# MSP.net
KiCad netlist of a schematic drawn in Altium Designer
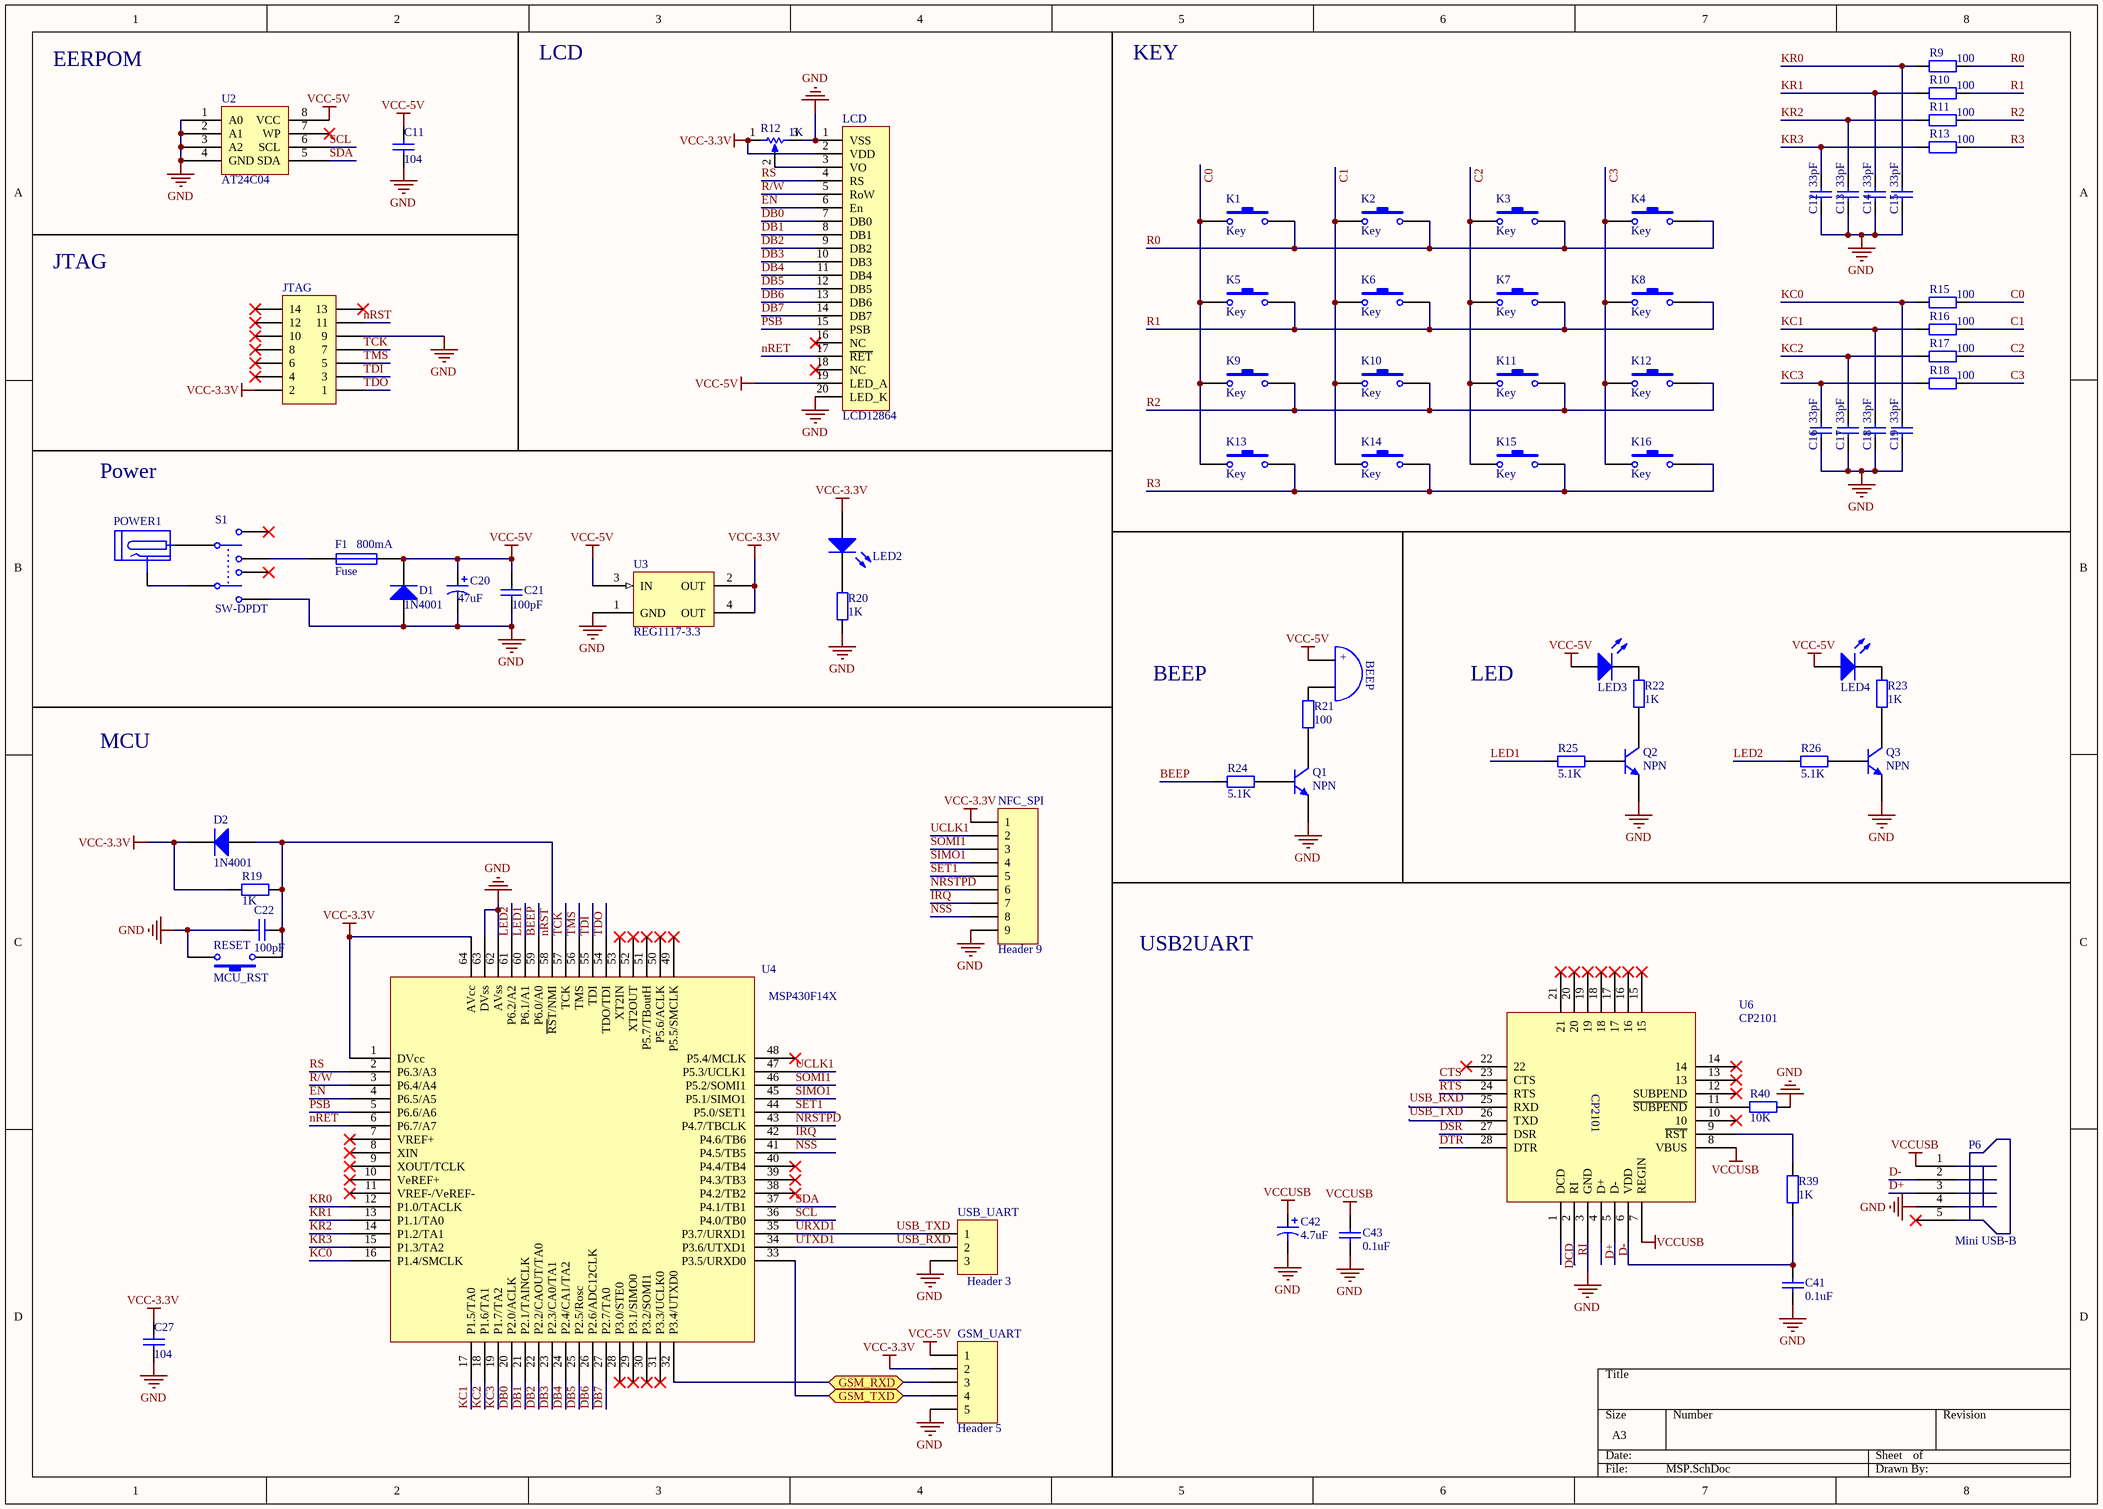
[diagram p0: MSP.SchDoc]

(export (version "E")
  (design (tool "Eeschema 10.0.6"))
  (components
    (comp (ref "BEEP1") (value "BEEP") (footprint "BEEP") (libsource (lib "common") (part "BEEP")))
    (comp (ref "C11")
      (value "104")
      (footprint "1608[0603]")
      (description "Capacitor")
      (fields (field (name "Comment") "Cap") (field (name "PUBLISHER") "Altium Limited"))
      (libsource (lib "common") (part "Cap"))
    )
    (comp (ref "C12")
      (value "33pF")
      (footprint "1608[0603]")
      (description "Capacitor")
      (fields (field (name "Comment") "Cap") (field (name "PUBLISHER") "Altium Limited"))
      (libsource (lib "common") (part "Cap"))
    )
    (comp (ref "C13")
      (value "33pF")
      (footprint "1608[0603]")
      (description "Capacitor")
      (fields (field (name "Comment") "Cap") (field (name "PUBLISHER") "Altium Limited"))
      (libsource (lib "common") (part "Cap"))
    )
    (comp (ref "C14")
      (value "33pF")
      (footprint "1608[0603]")
      (description "Capacitor")
      (fields (field (name "Comment") "Cap") (field (name "PUBLISHER") "Altium Limited"))
      (libsource (lib "common") (part "Cap"))
    )
    (comp (ref "C15")
      (value "33pF")
      (footprint "1608[0603]")
      (description "Capacitor")
      (fields (field (name "Comment") "Cap") (field (name "PUBLISHER") "Altium Limited"))
      (libsource (lib "common") (part "Cap"))
    )
    (comp (ref "C16")
      (value "33pF")
      (footprint "1608[0603]")
      (description "Capacitor")
      (fields (field (name "Comment") "Cap") (field (name "PUBLISHER") "Altium Limited"))
      (libsource (lib "common") (part "Cap"))
    )
    (comp (ref "C17")
      (value "33pF")
      (footprint "1608[0603]")
      (description "Capacitor")
      (fields (field (name "Comment") "Cap") (field (name "PUBLISHER") "Altium Limited"))
      (libsource (lib "common") (part "Cap"))
    )
    (comp (ref "C18")
      (value "33pF")
      (footprint "1608[0603]")
      (description "Capacitor")
      (fields (field (name "Comment") "Cap") (field (name "PUBLISHER") "Altium Limited"))
      (libsource (lib "common") (part "Cap"))
    )
    (comp (ref "C19")
      (value "33pF")
      (footprint "1608[0603]")
      (description "Capacitor")
      (fields (field (name "Comment") "Cap") (field (name "PUBLISHER") "Altium Limited"))
      (libsource (lib "common") (part "Cap"))
    )
    (comp (ref "C20")
      (value "47uF")
      (footprint "Standard:B")
      (description "Polarized Capacitor (Axial)")
      (fields (field (name "Comment") "CAP POL") (field (name "PUBLISHER") "Altium Limited"))
      (libsource (lib "common") (part "CAP POL"))
    )
    (comp (ref "C21")
      (value "100pF")
      (footprint "1608[0603]")
      (description "Capacitor")
      (fields (field (name "Comment") "Cap") (field (name "PUBLISHER") "Altium Limited"))
      (libsource (lib "common") (part "Cap"))
    )
    (comp (ref "C22")
      (value "100pF")
      (footprint "1608[0603]")
      (description "Capacitor")
      (fields (field (name "Comment") "Cap") (field (name "PUBLISHER") "Altium Limited"))
      (libsource (lib "common") (part "Cap"))
    )
    (comp (ref "C27")
      (value "104")
      (footprint "1608[0603]")
      (description "Capacitor")
      (fields (field (name "Comment") "Cap") (field (name "PUBLISHER") "Altium Limited"))
      (libsource (lib "common") (part "Cap"))
    )
    (comp (ref "C41")
      (value "0.1uF")
      (footprint "1608[0603]")
      (description "Capacitor")
      (fields (field (name "Comment") "Cap") (field (name "PUBLISHER") "Altium Limited"))
      (libsource (lib "common") (part "Cap"))
    )
    (comp (ref "C42")
      (value "4.7uF")
      (footprint "Standard:B")
      (description "Polarized Capacitor (Axial)")
      (fields (field (name "Comment") "CAP POL") (field (name "PUBLISHER") "Altium Limited"))
      (libsource (lib "common") (part "CAP POL"))
    )
    (comp (ref "C43")
      (value "0.1uF")
      (footprint "1608[0603]")
      (description "Capacitor")
      (fields (field (name "Comment") "Cap") (field (name "PUBLISHER") "Altium Limited"))
      (libsource (lib "common") (part "Cap"))
    )
    (comp (ref "D1")
      (value "1N4001")
      (footprint "1608[0603] - POL")
      (description "1 Amp General Purpose Rectifier")
      (fields (field (name "PUBLISHER") "Altium Limited"))
      (libsource (lib "common") (part "Diode 1N4001"))
    )
    (comp (ref "D2")
      (value "1N4001")
      (footprint "1608[0603] - POL")
      (description "1 Amp General Purpose Rectifier")
      (fields (field (name "PUBLISHER") "Altium Limited"))
      (libsource (lib "common") (part "Diode 1N4001"))
    )
    (comp (ref "F1")
      (value "Fuse")
      (footprint "2012[0805]")
      (fields (field (name "CURRENT") "800mA"))
      (libsource (lib "common") (part "FUSE1"))
    )
    (comp (ref "GSM_UART")
      (value "Header 5")
      (footprint "HDR1X5")
      (description "Header, 5-Pin")
      (fields (field (name "PUBLISHER") "Altium Limited"))
      (libsource (lib "Miscellaneous Connectors") (part "Header 5"))
    )
    (comp (ref "JTAG")
      (value "Header 7X2H")
      (footprint "HDR2X7H")
      (description "Header, 7-Pin, Dual row, Right Angle")
      (fields (field (name "PUBLISHER") "Altium Limited"))
      (libsource (lib "Miscellaneous Connectors") (part "Header 7X2H"))
    )
    (comp (ref "K1") (value "Key") (footprint "Key-4") (libsource (lib "*") (part "SW-PB")))
    (comp (ref "K2") (value "Key") (footprint "Key-4") (libsource (lib "common") (part "SW-PB")))
    (comp (ref "K3") (value "Key") (footprint "Key-4") (libsource (lib "common") (part "SW-PB")))
    (comp (ref "K4") (value "Key") (footprint "Key-4") (libsource (lib "common") (part "SW-PB")))
    (comp (ref "K5") (value "Key") (footprint "Key-4") (libsource (lib "common") (part "SW-PB")))
    (comp (ref "K6") (value "Key") (footprint "Key-4") (libsource (lib "common") (part "SW-PB")))
    (comp (ref "K7") (value "Key") (footprint "Key-4") (libsource (lib "common") (part "SW-PB")))
    (comp (ref "K8") (value "Key") (footprint "Key-4") (libsource (lib "common") (part "SW-PB")))
    (comp (ref "K9") (value "Key") (footprint "Key-4") (libsource (lib "common") (part "SW-PB")))
    (comp (ref "K10") (value "Key") (footprint "Key-4") (libsource (lib "common") (part "SW-PB")))
    (comp (ref "K11") (value "Key") (footprint "Key-4") (libsource (lib "common") (part "SW-PB")))
    (comp (ref "K12") (value "Key") (footprint "Key-4") (libsource (lib "common") (part "SW-PB")))
    (comp (ref "K13") (value "Key") (footprint "Key-4") (libsource (lib "common") (part "SW-PB")))
    (comp (ref "K14") (value "Key") (footprint "Key-4") (libsource (lib "common") (part "SW-PB")))
    (comp (ref "K15") (value "Key") (footprint "Key-4") (libsource (lib "common") (part "SW-PB")))
    (comp (ref "K16") (value "Key") (footprint "Key-4") (libsource (lib "common") (part "SW-PB")))
    (comp (ref "LCD") (value "LCD12864") (footprint "LCD-20PIN") (libsource (lib "*") (part "LCD12864")))
    (comp (ref "LED2") (value "LED") (footprint "2012[0805] - POL") (libsource (lib "common") (part "LED")))
    (comp (ref "LED3") (value "LED") (footprint "2012[0805] - POL") (libsource (lib "common") (part "LED")))
    (comp (ref "LED4") (value "LED") (footprint "2012[0805] - POL") (libsource (lib "common") (part "LED")))
    (comp (ref "NFC_SPI")
      (value "Header 9")
      (footprint "HDR1X9")
      (description "Header, 9-Pin")
      (fields (field (name "PUBLISHER") "Altium Limited"))
      (libsource (lib "Miscellaneous Connectors") (part "Header 9"))
    )
    (comp (ref "P6")
      (value "Mini USB-B")
      (footprint "MINI USB-501")
      (description "Mini USB Type B")
      (libsource (lib "USB2UART") (part "USB"))
    )
    (comp (ref "POWER1") (value "POWER") (footprint "POWER") (libsource (lib "51ExpBoard") (part "POWER")))
    (comp (ref "Q1") (value "NPN") (footprint "SOT23-3L") (libsource (lib "common") (part "NPN")))
    (comp (ref "Q2") (value "NPN") (footprint "SOT23-3L") (libsource (lib "common") (part "NPN")))
    (comp (ref "Q3") (value "NPN") (footprint "SOT23-3L") (libsource (lib "common") (part "NPN")))
    (comp (ref "R9")
      (value "100")
      (footprint "1608[0603]")
      (description "Resistor")
      (fields (field (name "Comment") "RES") (field (name "PUBLISHER") "Altium Limited"))
      (libsource (lib "common") (part "RES"))
    )
    (comp (ref "R10")
      (value "100")
      (footprint "1608[0603]")
      (description "Resistor")
      (fields (field (name "Comment") "RES") (field (name "PUBLISHER") "Altium Limited"))
      (libsource (lib "common") (part "RES"))
    )
    (comp (ref "R11")
      (value "100")
      (footprint "1608[0603]")
      (description "Resistor")
      (fields (field (name "Comment") "RES") (field (name "PUBLISHER") "Altium Limited"))
      (libsource (lib "common") (part "RES"))
    )
    (comp (ref "R12")
      (value "1K")
      (footprint "VR5")
      (description "Potentiometer")
      (fields (field (name "Comment") "RPot") (field (name "PUBLISHER") "Altium Limited"))
      (libsource (lib "Miscellaneous Devices") (part "RPot"))
    )
    (comp (ref "R13")
      (value "100")
      (footprint "1608[0603]")
      (description "Resistor")
      (fields (field (name "Comment") "RES") (field (name "PUBLISHER") "Altium Limited"))
      (libsource (lib "common") (part "RES"))
    )
    (comp (ref "R15")
      (value "100")
      (footprint "1608[0603]")
      (description "Resistor")
      (fields (field (name "Comment") "RES") (field (name "PUBLISHER") "Altium Limited"))
      (libsource (lib "common") (part "RES"))
    )
    (comp (ref "R16")
      (value "100")
      (footprint "1608[0603]")
      (description "Resistor")
      (fields (field (name "Comment") "RES") (field (name "PUBLISHER") "Altium Limited"))
      (libsource (lib "common") (part "RES"))
    )
    (comp (ref "R17")
      (value "100")
      (footprint "1608[0603]")
      (description "Resistor")
      (fields (field (name "Comment") "RES") (field (name "PUBLISHER") "Altium Limited"))
      (libsource (lib "common") (part "RES"))
    )
    (comp (ref "R18")
      (value "100")
      (footprint "1608[0603]")
      (description "Resistor")
      (fields (field (name "Comment") "RES") (field (name "PUBLISHER") "Altium Limited"))
      (libsource (lib "common") (part "RES"))
    )
    (comp (ref "R19")
      (value "1K")
      (footprint "1608[0603]")
      (description "Resistor")
      (fields (field (name "Comment") "Res") (field (name "PUBLISHER") "Altium Limited"))
      (libsource (lib "") (part "RES_2"))
    )
    (comp (ref "R20")
      (value "1K")
      (footprint "1608[0603]")
      (description "Resistor")
      (fields (field (name "Comment") "Res") (field (name "PUBLISHER") "Altium Limited"))
      (libsource (lib "") (part "RES_1"))
    )
    (comp (ref "R21")
      (value "100")
      (footprint "1608[0603]")
      (description "Resistor")
      (fields (field (name "Comment") "Res") (field (name "PUBLISHER") "Altium Limited"))
      (libsource (lib "") (part "RES_1"))
    )
    (comp (ref "R22")
      (value "1K")
      (footprint "1608[0603]")
      (description "Resistor")
      (fields (field (name "Comment") "Res") (field (name "PUBLISHER") "Altium Limited"))
      (libsource (lib "") (part "RES_1"))
    )
    (comp (ref "R23")
      (value "1K")
      (footprint "1608[0603]")
      (description "Resistor")
      (fields (field (name "Comment") "Res") (field (name "PUBLISHER") "Altium Limited"))
      (libsource (lib "") (part "RES_1"))
    )
    (comp (ref "R24")
      (value "5.1K")
      (footprint "1608[0603]")
      (description "Resistor")
      (fields (field (name "Comment") "Res") (field (name "PUBLISHER") "Altium Limited"))
      (libsource (lib "common") (part "RES"))
    )
    (comp (ref "R25")
      (value "5.1K")
      (footprint "1608[0603]")
      (description "Resistor")
      (fields (field (name "Comment") "Res") (field (name "PUBLISHER") "Altium Limited"))
      (libsource (lib "common") (part "RES"))
    )
    (comp (ref "R26")
      (value "5.1K")
      (footprint "1608[0603]")
      (description "Resistor")
      (fields (field (name "Comment") "Res") (field (name "PUBLISHER") "Altium Limited"))
      (libsource (lib "common") (part "RES"))
    )
    (comp (ref "R39")
      (value "1K")
      (footprint "1608[0603]")
      (description "Resistor")
      (fields (field (name "Comment") "Res") (field (name "PUBLISHER") "Altium Limited"))
      (libsource (lib "") (part "RES_3"))
    )
    (comp (ref "R40")
      (value "10K")
      (footprint "1608[0603]")
      (description "Resistor")
      (fields (field (name "Comment") "Res") (field (name "PUBLISHER") "Altium Limited"))
      (libsource (lib "common") (part "RES"))
    )
    (comp (ref "RESET") (value "MCU_RST") (footprint "Key-4") (libsource (lib "common") (part "SW-PB")))
    (comp (ref "S1")
      (value "SW-DPDT")
      (footprint "SW-DPDT")
      (description "Double-Pole, Double-Throw Switch")
      (fields (field (name "PUBLISHER") "Altium Limited"))
      (libsource (lib "common") (part "SW-DPDT"))
    )
    (comp (ref "U2")
      (value "AT24C04")
      (footprint "SOIC127P600-8AN")
      (libsource (lib "common") (part "AT24C04"))
    )
    (comp (ref "U3")
      (value "REG1117-3.3")
      (footprint "SOT223")
      (libsource (lib "MYSELF") (part "REG1117-3.3"))
    )
    (comp (ref "U4")
      (value "MSP430F14X")
      (footprint "SQFP50P1200X1200-64N")
      (libsource (lib "*") (part "MSP430F14X"))
    )
    (comp (ref "U6")
      (value "CP2101")
      (footprint "QFN50P500X500-28VAN")
      (libsource (lib "USB2UART") (part "CP2101"))
    )
    (comp (ref "USB_UART")
      (value "Header 3")
      (footprint "HDR1X3")
      (description "Header, 3-Pin")
      (fields (field (name "PUBLISHER") "Altium Limited"))
      (libsource (lib "Miscellaneous Connectors") (part "Header 3"))
    )
  )
  (nets
    (net (code "1") (name "/BEEP") (class "Default")
      (node (ref "R24") (pin "1") (pinfunction "1_1") (pintype "passive"))
      (node (ref "U4") (pin "59") (pinfunction "P6.0/A0_59") (pintype "power_in"))
    )
    (net (code "2") (name "/C0") (class "Default")
      (node (ref "K1") (pin "1") (pinfunction "1_1") (pintype "passive"))
      (node (ref "K13") (pin "1") (pinfunction "1_1") (pintype "passive"))
      (node (ref "K5") (pin "1") (pinfunction "1_1") (pintype "passive"))
      (node (ref "K9") (pin "1") (pinfunction "1_1") (pintype "passive"))
      (node (ref "R15") (pin "2") (pinfunction "2_2") (pintype "passive"))
    )
    (net (code "3") (name "/C1") (class "Default")
      (node (ref "K10") (pin "1") (pinfunction "1_1") (pintype "passive"))
      (node (ref "K14") (pin "1") (pinfunction "1_1") (pintype "passive"))
      (node (ref "K2") (pin "1") (pinfunction "1_1") (pintype "passive"))
      (node (ref "K6") (pin "1") (pinfunction "1_1") (pintype "passive"))
      (node (ref "R16") (pin "2") (pinfunction "2_2") (pintype "passive"))
    )
    (net (code "4") (name "/C2") (class "Default")
      (node (ref "K11") (pin "1") (pinfunction "1_1") (pintype "passive"))
      (node (ref "K15") (pin "1") (pinfunction "1_1") (pintype "passive"))
      (node (ref "K3") (pin "1") (pinfunction "1_1") (pintype "passive"))
      (node (ref "K7") (pin "1") (pinfunction "1_1") (pintype "passive"))
      (node (ref "R17") (pin "2") (pinfunction "2_2") (pintype "passive"))
    )
    (net (code "5") (name "/C3") (class "Default")
      (node (ref "K12") (pin "1") (pinfunction "1_1") (pintype "passive"))
      (node (ref "K16") (pin "1") (pinfunction "1_1") (pintype "passive"))
      (node (ref "K4") (pin "1") (pinfunction "1_1") (pintype "passive"))
      (node (ref "K8") (pin "1") (pinfunction "1_1") (pintype "passive"))
      (node (ref "R18") (pin "2") (pinfunction "2_2") (pintype "passive"))
    )
    (net (code "6") (name "/CTS") (class "Default")
      (node (ref "U6") (pin "23") (pinfunction "CTS_23") (pintype "passive"))
    )
    (net (code "7") (name "/D+") (class "Default")
      (node (ref "P6") (pin "3") (pinfunction "3_3") (pintype "passive"))
      (node (ref "U6") (pin "4") (pinfunction "D+_4") (pintype "passive"))
    )
    (net (code "8") (name "/D-") (class "Default")
      (node (ref "P6") (pin "2") (pinfunction "2_2") (pintype "passive"))
      (node (ref "U6") (pin "5") (pinfunction "D-_5") (pintype "passive"))
    )
    (net (code "9") (name "/DB0") (class "Default")
      (node (ref "LCD") (pin "7") (pinfunction "DB0_7") (pintype "passive"))
      (node (ref "U4") (pin "20") (pinfunction "P2.0/ACLK_20") (pintype "power_in"))
    )
    (net (code "10") (name "/DB1") (class "Default")
      (node (ref "LCD") (pin "8") (pinfunction "DB1_8") (pintype "passive"))
      (node (ref "U4") (pin "21") (pinfunction "P2.1/TAINCLK_21") (pintype "power_in"))
    )
    (net (code "11") (name "/DB2") (class "Default")
      (node (ref "LCD") (pin "9") (pinfunction "DB2_9") (pintype "passive"))
      (node (ref "U4") (pin "22") (pinfunction "P2.2/CAOUT/TA0_22") (pintype "power_in"))
    )
    (net (code "12") (name "/DB3") (class "Default")
      (node (ref "LCD") (pin "10") (pinfunction "DB3_10") (pintype "passive"))
      (node (ref "U4") (pin "23") (pinfunction "P2.3/CA0/TA1_23") (pintype "power_in"))
    )
    (net (code "13") (name "/DB4") (class "Default")
      (node (ref "LCD") (pin "11") (pinfunction "DB4_11") (pintype "passive"))
      (node (ref "U4") (pin "24") (pinfunction "P2.4/CA1/TA2_24") (pintype "power_in"))
    )
    (net (code "14") (name "/DB5") (class "Default")
      (node (ref "LCD") (pin "12") (pinfunction "DB5_12") (pintype "passive"))
      (node (ref "U4") (pin "25") (pinfunction "P2.5/Rosc_25") (pintype "power_in"))
    )
    (net (code "15") (name "/DB6") (class "Default")
      (node (ref "LCD") (pin "13") (pinfunction "DB6_13") (pintype "passive"))
      (node (ref "U4") (pin "26") (pinfunction "P2.6/ADC12CLK_26") (pintype "power_in"))
    )
    (net (code "16") (name "/DB7") (class "Default")
      (node (ref "LCD") (pin "14") (pinfunction "DB7_14") (pintype "passive"))
      (node (ref "U4") (pin "27") (pinfunction "P2.7/TA0_27") (pintype "power_in"))
    )
    (net (code "17") (name "/DCD") (class "Default")
      (node (ref "U6") (pin "1") (pinfunction "DCD_1") (pintype "passive"))
    )
    (net (code "18") (name "/DSR") (class "Default")
      (node (ref "U6") (pin "27") (pinfunction "DSR_27") (pintype "passive"))
    )
    (net (code "19") (name "/DTR") (class "Default")
      (node (ref "U6") (pin "28") (pinfunction "DTR_28") (pintype "passive"))
    )
    (net (code "20") (name "/EN") (class "Default")
      (node (ref "LCD") (pin "6") (pinfunction "En_6") (pintype "passive"))
      (node (ref "U4") (pin "4") (pinfunction "P6.5/A5_4") (pintype "power_in"))
    )
    (net (code "21") (name "/GSM_RXD") (class "Default")
      (node (ref "GSM_UART") (pin "3") (pinfunction "3_3") (pintype "passive"))
      (node (ref "U4") (pin "32") (pinfunction "P3.4/UTXD0_32") (pintype "power_in"))
    )
    (net (code "22") (name "/GSM_TXD") (class "Default")
      (node (ref "GSM_UART") (pin "4") (pinfunction "4_4") (pintype "passive"))
      (node (ref "U4") (pin "33") (pinfunction "P3.5/URXD0_33") (pintype "power_in"))
    )
    (net (code "23") (name "/IRQ") (class "Default")
      (node (ref "NFC_SPI") (pin "7") (pinfunction "7_7") (pintype "passive"))
      (node (ref "U4") (pin "42") (pinfunction "P4.6/TB6_42") (pintype "power_in"))
    )
    (net (code "24") (name "/KC0") (class "Default")
      (node (ref "C19") (pin "1") (pinfunction "1_1") (pintype "passive"))
      (node (ref "R15") (pin "1") (pinfunction "1_1") (pintype "passive"))
      (node (ref "U4") (pin "16") (pinfunction "P1.4/SMCLK_16") (pintype "power_in"))
    )
    (net (code "25") (name "/KC1") (class "Default")
      (node (ref "C18") (pin "1") (pinfunction "1_1") (pintype "passive"))
      (node (ref "R16") (pin "1") (pinfunction "1_1") (pintype "passive"))
      (node (ref "U4") (pin "17") (pinfunction "P1.5/TA0_17") (pintype "power_in"))
    )
    (net (code "26") (name "/KC2") (class "Default")
      (node (ref "C17") (pin "1") (pinfunction "1_1") (pintype "passive"))
      (node (ref "R17") (pin "1") (pinfunction "1_1") (pintype "passive"))
      (node (ref "U4") (pin "18") (pinfunction "P1.6/TA1_18") (pintype "power_in"))
    )
    (net (code "27") (name "/KC3") (class "Default")
      (node (ref "C16") (pin "1") (pinfunction "1_1") (pintype "passive"))
      (node (ref "R18") (pin "1") (pinfunction "1_1") (pintype "passive"))
      (node (ref "U4") (pin "19") (pinfunction "P1.7/TA2_19") (pintype "power_in"))
    )
    (net (code "28") (name "/KR0") (class "Default")
      (node (ref "C15") (pin "1") (pinfunction "1_1") (pintype "passive"))
      (node (ref "R9") (pin "1") (pinfunction "1_1") (pintype "passive"))
      (node (ref "U4") (pin "12") (pinfunction "P1.0/TACLK_12") (pintype "power_in"))
    )
    (net (code "29") (name "/KR1") (class "Default")
      (node (ref "C14") (pin "1") (pinfunction "1_1") (pintype "passive"))
      (node (ref "R10") (pin "1") (pinfunction "1_1") (pintype "passive"))
      (node (ref "U4") (pin "13") (pinfunction "P1.1/TA0_13") (pintype "power_in"))
    )
    (net (code "30") (name "/KR2") (class "Default")
      (node (ref "C13") (pin "1") (pinfunction "1_1") (pintype "passive"))
      (node (ref "R11") (pin "1") (pinfunction "1_1") (pintype "passive"))
      (node (ref "U4") (pin "14") (pinfunction "P1.2/TA1_14") (pintype "power_in"))
    )
    (net (code "31") (name "/KR3") (class "Default")
      (node (ref "C12") (pin "1") (pinfunction "1_1") (pintype "passive"))
      (node (ref "R13") (pin "1") (pinfunction "1_1") (pintype "passive"))
      (node (ref "U4") (pin "15") (pinfunction "P1.3/TA2_15") (pintype "power_in"))
    )
    (net (code "32") (name "/LED1") (class "Default")
      (node (ref "R25") (pin "1") (pinfunction "1_1") (pintype "passive"))
      (node (ref "U4") (pin "60") (pinfunction "P6.1/A1_60") (pintype "power_in"))
    )
    (net (code "33") (name "/LED2") (class "Default")
      (node (ref "R26") (pin "1") (pinfunction "1_1") (pintype "passive"))
      (node (ref "U4") (pin "61") (pinfunction "P6.2/A2_61") (pintype "power_in"))
    )
    (net (code "34") (name "/NRSTPD") (class "Default")
      (node (ref "NFC_SPI") (pin "6") (pinfunction "6_6") (pintype "passive"))
      (node (ref "U4") (pin "43") (pinfunction "P4.7/TBCLK_43") (pintype "power_in"))
    )
    (net (code "35") (name "/NSS") (class "Default")
      (node (ref "NFC_SPI") (pin "8") (pinfunction "8_8") (pintype "passive"))
      (node (ref "U4") (pin "41") (pinfunction "P4.5/TB5_41") (pintype "power_in"))
    )
    (net (code "36") (name "/PSB") (class "Default")
      (node (ref "LCD") (pin "15") (pinfunction "PSB_15") (pintype "passive"))
      (node (ref "U4") (pin "5") (pinfunction "P6.6/A6_5") (pintype "power_in"))
    )
    (net (code "37") (name "/R0") (class "Default")
      (node (ref "K1") (pin "2") (pinfunction "2_2") (pintype "passive"))
      (node (ref "K2") (pin "2") (pinfunction "2_2") (pintype "passive"))
      (node (ref "K3") (pin "2") (pinfunction "2_2") (pintype "passive"))
      (node (ref "K4") (pin "2") (pinfunction "2_2") (pintype "passive"))
      (node (ref "R9") (pin "2") (pinfunction "2_2") (pintype "passive"))
    )
    (net (code "38") (name "/R1") (class "Default")
      (node (ref "K5") (pin "2") (pinfunction "2_2") (pintype "passive"))
      (node (ref "K6") (pin "2") (pinfunction "2_2") (pintype "passive"))
      (node (ref "K7") (pin "2") (pinfunction "2_2") (pintype "passive"))
      (node (ref "K8") (pin "2") (pinfunction "2_2") (pintype "passive"))
      (node (ref "R10") (pin "2") (pinfunction "2_2") (pintype "passive"))
    )
    (net (code "39") (name "/R2") (class "Default")
      (node (ref "K10") (pin "2") (pinfunction "2_2") (pintype "passive"))
      (node (ref "K11") (pin "2") (pinfunction "2_2") (pintype "passive"))
      (node (ref "K12") (pin "2") (pinfunction "2_2") (pintype "passive"))
      (node (ref "K9") (pin "2") (pinfunction "2_2") (pintype "passive"))
      (node (ref "R11") (pin "2") (pinfunction "2_2") (pintype "passive"))
    )
    (net (code "40") (name "/R3") (class "Default")
      (node (ref "K13") (pin "2") (pinfunction "2_2") (pintype "passive"))
      (node (ref "K14") (pin "2") (pinfunction "2_2") (pintype "passive"))
      (node (ref "K15") (pin "2") (pinfunction "2_2") (pintype "passive"))
      (node (ref "K16") (pin "2") (pinfunction "2_2") (pintype "passive"))
      (node (ref "R13") (pin "2") (pinfunction "2_2") (pintype "passive"))
    )
    (net (code "41") (name "/RI") (class "Default")
      (node (ref "U6") (pin "2") (pinfunction "RI_2") (pintype "passive"))
    )
    (net (code "42") (name "/RS") (class "Default")
      (node (ref "LCD") (pin "4") (pinfunction "RS_4") (pintype "passive"))
      (node (ref "U4") (pin "2") (pinfunction "P6.3/A3_2") (pintype "power_in"))
    )
    (net (code "43") (name "/RTS") (class "Default")
      (node (ref "U6") (pin "24") (pinfunction "RTS_24") (pintype "passive"))
    )
    (net (code "44") (name "/R{slash}W") (class "Default")
      (node (ref "LCD") (pin "5") (pinfunction "RoW_5") (pintype "passive"))
      (node (ref "U4") (pin "3") (pinfunction "P6.4/A4_3") (pintype "power_in"))
    )
    (net (code "45") (name "/SCL") (class "Default")
      (node (ref "U2") (pin "6") (pinfunction "SCL_6") (pintype "passive"))
      (node (ref "U4") (pin "36") (pinfunction "P4.0/TB0_36") (pintype "power_in"))
    )
    (net (code "46") (name "/SDA") (class "Default")
      (node (ref "U2") (pin "5") (pinfunction "SDA_5") (pintype "passive"))
      (node (ref "U4") (pin "37") (pinfunction "P4.1/TB1_37") (pintype "power_in"))
    )
    (net (code "47") (name "/SET1") (class "Default")
      (node (ref "NFC_SPI") (pin "5") (pinfunction "5_5") (pintype "passive"))
      (node (ref "U4") (pin "44") (pinfunction "P5.0/SET1_44") (pintype "power_in"))
    )
    (net (code "48") (name "/SIMO1") (class "Default")
      (node (ref "NFC_SPI") (pin "4") (pinfunction "4_4") (pintype "passive"))
      (node (ref "U4") (pin "45") (pinfunction "P5.1/SIMO1_45") (pintype "power_in"))
    )
    (net (code "49") (name "/SOMI1") (class "Default")
      (node (ref "NFC_SPI") (pin "3") (pinfunction "3_3") (pintype "passive"))
      (node (ref "U4") (pin "46") (pinfunction "P5.2/SOMI1_46") (pintype "power_in"))
    )
    (net (code "50") (name "/TCK") (class "Default")
      (node (ref "JTAG") (pin "7") (pinfunction "7_7") (pintype "passive"))
      (node (ref "U4") (pin "57") (pinfunction "TCK_57") (pintype "power_in"))
    )
    (net (code "51") (name "/TDI") (class "Default")
      (node (ref "JTAG") (pin "3") (pinfunction "3_3") (pintype "passive"))
      (node (ref "U4") (pin "55") (pinfunction "TDI_55") (pintype "power_in"))
    )
    (net (code "52") (name "/TDO") (class "Default")
      (node (ref "JTAG") (pin "1") (pinfunction "1_1") (pintype "passive"))
      (node (ref "U4") (pin "54") (pinfunction "TDO/TDI_54") (pintype "power_in"))
    )
    (net (code "53") (name "/TMS") (class "Default")
      (node (ref "JTAG") (pin "5") (pinfunction "5_5") (pintype "passive"))
      (node (ref "U4") (pin "56") (pinfunction "TMS_56") (pintype "power_in"))
    )
    (net (code "54") (name "/UCLK1") (class "Default")
      (node (ref "NFC_SPI") (pin "2") (pinfunction "2_2") (pintype "passive"))
      (node (ref "U4") (pin "47") (pinfunction "P5.3/UCLK1_47") (pintype "power_in"))
    )
    (net (code "55") (name "/URXD1") (class "Default")
      (node (ref "U4") (pin "35") (pinfunction "P3.7/URXD1_35") (pintype "power_in"))
      (node (ref "U6") (pin "26") (pinfunction "TXD_26") (pintype "passive"))
      (node (ref "USB_UART") (pin "1") (pinfunction "1_1") (pintype "passive"))
    )
    (net (code "56") (name "/USB_RXD") (class "Default")
      (node (ref "U4") (pin "34") (pinfunction "P3.6/UTXD1_34") (pintype "power_in"))
      (node (ref "U6") (pin "25") (pinfunction "RXD_25") (pintype "passive"))
      (node (ref "USB_UART") (pin "2") (pinfunction "2_2") (pintype "passive"))
    )
    (net (code "57") (name "/nRET") (class "Default")
      (node (ref "LCD") (pin "17") (pinfunction "~{RET}_17") (pintype "passive"))
      (node (ref "U4") (pin "6") (pinfunction "P6.7/A7_6") (pintype "power_in"))
    )
    (net (code "58") (name "/nRST") (class "Default")
      (node (ref "C22") (pin "1") (pinfunction "1_1") (pintype "passive"))
      (node (ref "D2") (pin "1") (pinfunction "A_1") (pintype "passive"))
      (node (ref "JTAG") (pin "11") (pinfunction "11_11") (pintype "passive"))
      (node (ref "R19") (pin "1") (pinfunction "1_1") (pintype "passive"))
      (node (ref "RESET") (pin "1") (pinfunction "1_1") (pintype "passive"))
      (node (ref "U4") (pin "58") (pinfunction "~{RS}T/NMI_58") (pintype "power_in"))
    )
    (net (code "59") (name "GND") (class "Default")
      (node (ref "C11") (pin "1") (pinfunction "1_1") (pintype "passive"))
      (node (ref "C12") (pin "2") (pinfunction "2_2") (pintype "passive"))
      (node (ref "C13") (pin "2") (pinfunction "2_2") (pintype "passive"))
      (node (ref "C14") (pin "2") (pinfunction "2_2") (pintype "passive"))
      (node (ref "C15") (pin "2") (pinfunction "2_2") (pintype "passive"))
      (node (ref "C16") (pin "2") (pinfunction "2_2") (pintype "passive"))
      (node (ref "C17") (pin "2") (pinfunction "2_2") (pintype "passive"))
      (node (ref "C18") (pin "2") (pinfunction "2_2") (pintype "passive"))
      (node (ref "C19") (pin "2") (pinfunction "2_2") (pintype "passive"))
      (node (ref "C20") (pin "2") (pinfunction "2_2") (pintype "passive"))
      (node (ref "C21") (pin "1") (pinfunction "1_1") (pintype "passive"))
      (node (ref "C22") (pin "2") (pinfunction "2_2") (pintype "passive"))
      (node (ref "C27") (pin "1") (pinfunction "1_1") (pintype "passive"))
      (node (ref "C41") (pin "1") (pinfunction "1_1") (pintype "passive"))
      (node (ref "C42") (pin "2") (pinfunction "2_2") (pintype "passive"))
      (node (ref "C43") (pin "1") (pinfunction "1_1") (pintype "passive"))
      (node (ref "D1") (pin "1") (pinfunction "A_1") (pintype "passive"))
      (node (ref "GSM_UART") (pin "5") (pinfunction "5_5") (pintype "passive"))
      (node (ref "JTAG") (pin "9") (pinfunction "9_9") (pintype "passive"))
      (node (ref "LCD") (pin "1") (pinfunction "VSS_1") (pintype "passive"))
      (node (ref "LCD") (pin "20") (pinfunction "LED_K_20") (pintype "passive"))
      (node (ref "NFC_SPI") (pin "9") (pinfunction "9_9") (pintype "passive"))
      (node (ref "P6") (pin "4") (pinfunction "4_4") (pintype "passive"))
      (node (ref "Q1") (pin "3") (pinfunction "E_3") (pintype "passive"))
      (node (ref "Q2") (pin "3") (pinfunction "E_3") (pintype "passive"))
      (node (ref "Q3") (pin "3") (pinfunction "E_3") (pintype "passive"))
      (node (ref "R12") (pin "3") (pinfunction "BOT_3") (pintype "passive"))
      (node (ref "R20") (pin "2") (pinfunction "2_2") (pintype "passive"))
      (node (ref "R40") (pin "2") (pinfunction "2_2") (pintype "passive"))
      (node (ref "RESET") (pin "2") (pinfunction "2_2") (pintype "passive"))
      (node (ref "S1") (pin "6") (pinfunction "6_6") (pintype "passive"))
      (node (ref "U2") (pin "1") (pinfunction "A0_1") (pintype "passive"))
      (node (ref "U2") (pin "2") (pinfunction "A1_2") (pintype "passive"))
      (node (ref "U2") (pin "3") (pinfunction "A2_3") (pintype "passive"))
      (node (ref "U2") (pin "4") (pinfunction "GND_4") (pintype "passive"))
      (node (ref "U3") (pin "1") (pinfunction "GND_1") (pintype "passive"))
      (node (ref "U4") (pin "62") (pinfunction "AVss_62") (pintype "power_in"))
      (node (ref "U4") (pin "63") (pinfunction "DVss_63") (pintype "power_in"))
      (node (ref "U6") (pin "3") (pinfunction "GND_3") (pintype "passive"))
      (node (ref "USB_UART") (pin "3") (pinfunction "3_3") (pintype "passive"))
    )
    (net (code "60") (name "Net-(BEEP1-A)") (class "Default")
      (node (ref "BEEP1") (pin "2") (pinfunction "A_2") (pintype "passive"))
      (node (ref "R21") (pin "1") (pinfunction "1_1") (pintype "passive"))
    )
    (net (code "61") (name "Net-(F1-Pad1)") (class "Default")
      (node (ref "F1") (pin "1") (pinfunction "1_1") (pintype "passive"))
      (node (ref "S1") (pin "3") (pinfunction "3_3") (pintype "passive"))
    )
    (net (code "62") (name "Net-(LCD-VO)") (class "Default")
      (node (ref "LCD") (pin "3") (pinfunction "VO_3") (pintype "passive"))
      (node (ref "R12") (pin "2") (pinfunction "TAP_2") (pintype "passive"))
    )
    (net (code "63") (name "Net-(LED2-K)") (class "Default")
      (node (ref "LED2") (pin "2") (pinfunction "K_2") (pintype "passive"))
      (node (ref "R20") (pin "1") (pinfunction "1_1") (pintype "passive"))
    )
    (net (code "64") (name "Net-(LED3-K)") (class "Default")
      (node (ref "LED3") (pin "2") (pinfunction "K_2") (pintype "passive"))
      (node (ref "R22") (pin "1") (pinfunction "1_1") (pintype "passive"))
    )
    (net (code "65") (name "Net-(LED4-K)") (class "Default")
      (node (ref "LED4") (pin "2") (pinfunction "K_2") (pintype "passive"))
      (node (ref "R23") (pin "1") (pinfunction "1_1") (pintype "passive"))
    )
    (net (code "66") (name "Net-(POWER1-Pad1)") (class "Default")
      (node (ref "POWER1") (pin "1") (pinfunction "1_1") (pintype "power_in"))
      (node (ref "S1") (pin "1") (pinfunction "1_1") (pintype "passive"))
    )
    (net (code "67") (name "Net-(POWER1-Pad2)") (class "Default")
      (node (ref "POWER1") (pin "2") (pinfunction "2_2") (pintype "power_in"))
      (node (ref "S1") (pin "4") (pinfunction "4_4") (pintype "passive"))
    )
    (net (code "68") (name "Net-(Q1-B)") (class "Default")
      (node (ref "Q1") (pin "2") (pinfunction "B_2") (pintype "passive"))
      (node (ref "R24") (pin "2") (pinfunction "2_2") (pintype "passive"))
    )
    (net (code "69") (name "Net-(Q1-C)") (class "Default")
      (node (ref "Q1") (pin "1") (pinfunction "C_1") (pintype "passive"))
      (node (ref "R21") (pin "2") (pinfunction "2_2") (pintype "passive"))
    )
    (net (code "70") (name "Net-(Q2-B)") (class "Default")
      (node (ref "Q2") (pin "2") (pinfunction "B_2") (pintype "passive"))
      (node (ref "R25") (pin "2") (pinfunction "2_2") (pintype "passive"))
    )
    (net (code "71") (name "Net-(Q2-C)") (class "Default")
      (node (ref "Q2") (pin "1") (pinfunction "C_1") (pintype "passive"))
      (node (ref "R22") (pin "2") (pinfunction "2_2") (pintype "passive"))
    )
    (net (code "72") (name "Net-(Q3-B)") (class "Default")
      (node (ref "Q3") (pin "2") (pinfunction "B_2") (pintype "passive"))
      (node (ref "R26") (pin "2") (pinfunction "2_2") (pintype "passive"))
    )
    (net (code "73") (name "Net-(Q3-C)") (class "Default")
      (node (ref "Q3") (pin "1") (pinfunction "C_1") (pintype "passive"))
      (node (ref "R23") (pin "2") (pinfunction "2_2") (pintype "passive"))
    )
    (net (code "74") (name "Net-(U6-VDD)") (class "Default")
      (node (ref "C41") (pin "2") (pinfunction "2_2") (pintype "passive"))
      (node (ref "R39") (pin "1") (pinfunction "1_1") (pintype "passive"))
      (node (ref "U6") (pin "6") (pinfunction "VDD_6") (pintype "passive"))
    )
    (net (code "75") (name "Net-(U6-~{RST})") (class "Default")
      (node (ref "R39") (pin "2") (pinfunction "2_2") (pintype "passive"))
      (node (ref "U6") (pin "9") (pinfunction "~{RST}_9") (pintype "passive"))
    )
    (net (code "76") (name "Net-(U6-~{SUBPEND})") (class "Default")
      (node (ref "R40") (pin "1") (pinfunction "1_1") (pintype "passive"))
      (node (ref "U6") (pin "11") (pinfunction "~{SUBPEND}_11") (pintype "passive"))
    )
    (net (code "77") (name "VCC-3.3V") (class "Default")
      (node (ref "C27") (pin "2") (pinfunction "2_2") (pintype "passive"))
      (node (ref "D2") (pin "2") (pinfunction "K_2") (pintype "passive"))
      (node (ref "GSM_UART") (pin "2") (pinfunction "2_2") (pintype "passive"))
      (node (ref "JTAG") (pin "2") (pinfunction "2_2") (pintype "passive"))
      (node (ref "LCD") (pin "2") (pinfunction "VDD_2") (pintype "passive"))
      (node (ref "LED2") (pin "1") (pinfunction "A_1") (pintype "passive"))
      (node (ref "NFC_SPI") (pin "1") (pinfunction "1_1") (pintype "passive"))
      (node (ref "R12") (pin "1") (pinfunction "TOP_1") (pintype "passive"))
      (node (ref "R19") (pin "2") (pinfunction "2_2") (pintype "passive"))
      (node (ref "U3") (pin "2") (pinfunction "OUT_2") (pintype "power_in"))
      (node (ref "U3") (pin "4") (pinfunction "OUT_4") (pintype "power_in"))
      (node (ref "U4") (pin "1") (pinfunction "DVcc_1") (pintype "power_in"))
      (node (ref "U4") (pin "64") (pinfunction "AVcc_64") (pintype "power_in"))
    )
    (net (code "78") (name "VCC-5V") (class "Default")
      (node (ref "BEEP1") (pin "1") (pinfunction "B_1") (pintype "passive"))
      (node (ref "C11") (pin "2") (pinfunction "2_2") (pintype "passive"))
      (node (ref "C20") (pin "1") (pinfunction "1_1") (pintype "passive"))
      (node (ref "C21") (pin "2") (pinfunction "2_2") (pintype "passive"))
      (node (ref "D1") (pin "2") (pinfunction "K_2") (pintype "passive"))
      (node (ref "F1") (pin "2") (pinfunction "2_2") (pintype "passive"))
      (node (ref "GSM_UART") (pin "1") (pinfunction "1_1") (pintype "passive"))
      (node (ref "LCD") (pin "19") (pinfunction "LED_A_19") (pintype "passive"))
      (node (ref "LED3") (pin "1") (pinfunction "A_1") (pintype "passive"))
      (node (ref "LED4") (pin "1") (pinfunction "A_1") (pintype "passive"))
      (node (ref "U2") (pin "8") (pinfunction "VCC_8") (pintype "passive"))
      (node (ref "U3") (pin "3") (pinfunction "IN_3") (pintype "input"))
    )
    (net (code "79") (name "VCCUSB") (class "Default")
      (node (ref "C42") (pin "1") (pinfunction "1_1") (pintype "passive"))
      (node (ref "C43") (pin "2") (pinfunction "2_2") (pintype "passive"))
      (node (ref "P6") (pin "1") (pinfunction "1_1") (pintype "passive"))
      (node (ref "U6") (pin "7") (pinfunction "REGIN_7") (pintype "passive"))
      (node (ref "U6") (pin "8") (pinfunction "VBUS_8") (pintype "passive"))
    )
    (net (code "80") (name "unconnected-(JTAG-Pad4)") (class "Default")
      (node (ref "JTAG") (pin "4") (pinfunction "4_4") (pintype "passive+no_connect"))
    )
    (net (code "81") (name "unconnected-(JTAG-Pad6)") (class "Default")
      (node (ref "JTAG") (pin "6") (pinfunction "6_6") (pintype "passive+no_connect"))
    )
    (net (code "82") (name "unconnected-(JTAG-Pad8)") (class "Default")
      (node (ref "JTAG") (pin "8") (pinfunction "8_8") (pintype "passive+no_connect"))
    )
    (net (code "83") (name "unconnected-(JTAG-Pad10)") (class "Default")
      (node (ref "JTAG") (pin "10") (pinfunction "10_10") (pintype "passive+no_connect"))
    )
    (net (code "84") (name "unconnected-(JTAG-Pad12)") (class "Default")
      (node (ref "JTAG") (pin "12") (pinfunction "12_12") (pintype "passive+no_connect"))
    )
    (net (code "85") (name "unconnected-(JTAG-Pad13)") (class "Default")
      (node (ref "JTAG") (pin "13") (pinfunction "13_13") (pintype "passive+no_connect"))
    )
    (net (code "86") (name "unconnected-(JTAG-Pad14)") (class "Default")
      (node (ref "JTAG") (pin "14") (pinfunction "14_14") (pintype "passive+no_connect"))
    )
    (net (code "87") (name "unconnected-(LCD-NC-Pad16)") (class "Default")
      (node (ref "LCD") (pin "16") (pinfunction "NC_16") (pintype "passive+no_connect"))
    )
    (net (code "88") (name "unconnected-(LCD-NC-Pad18)") (class "Default")
      (node (ref "LCD") (pin "18") (pinfunction "NC_18") (pintype "passive+no_connect"))
    )
    (net (code "89") (name "unconnected-(P6-Pad5)") (class "Default")
      (node (ref "P6") (pin "5") (pinfunction "5_5") (pintype "passive+no_connect"))
    )
    (net (code "90") (name "unconnected-(S1-Pad2)") (class "Default")
      (node (ref "S1") (pin "2") (pinfunction "2_2") (pintype "passive+no_connect"))
    )
    (net (code "91") (name "unconnected-(S1-Pad5)") (class "Default")
      (node (ref "S1") (pin "5") (pinfunction "5_5") (pintype "passive+no_connect"))
    )
    (net (code "92") (name "unconnected-(U2-WP-Pad7)") (class "Default")
      (node (ref "U2") (pin "7") (pinfunction "WP_7") (pintype "passive+no_connect"))
    )
    (net (code "93") (name "unconnected-(U4-P3.0{slash}STE0-Pad28)") (class "Default")
      (node (ref "U4") (pin "28") (pinfunction "P3.0/STE0_28") (pintype "power_in+no_connect"))
    )
    (net (code "94") (name "unconnected-(U4-P3.1{slash}SIMO0-Pad29)") (class "Default")
      (node (ref "U4") (pin "29") (pinfunction "P3.1/SIMO0_29") (pintype "power_in+no_connect"))
    )
    (net (code "95") (name "unconnected-(U4-P3.2{slash}SOMI1-Pad30)") (class "Default")
      (node (ref "U4") (pin "30") (pinfunction "P3.2/SOMI1_30") (pintype "power_in+no_connect"))
    )
    (net (code "96") (name "unconnected-(U4-P3.3{slash}UCLK0-Pad31)") (class "Default")
      (node (ref "U4") (pin "31") (pinfunction "P3.3/UCLK0_31") (pintype "power_in+no_connect"))
    )
    (net (code "97") (name "unconnected-(U4-P4.2{slash}TB2-Pad38)") (class "Default")
      (node (ref "U4") (pin "38") (pinfunction "P4.2/TB2_38") (pintype "power_in+no_connect"))
    )
    (net (code "98") (name "unconnected-(U4-P4.3{slash}TB3-Pad39)") (class "Default")
      (node (ref "U4") (pin "39") (pinfunction "P4.3/TB3_39") (pintype "power_in+no_connect"))
    )
    (net (code "99") (name "unconnected-(U4-P4.4{slash}TB4-Pad40)") (class "Default")
      (node (ref "U4") (pin "40") (pinfunction "P4.4/TB4_40") (pintype "power_in+no_connect"))
    )
    (net (code "100") (name "unconnected-(U4-P5.4{slash}MCLK-Pad48)") (class "Default")
      (node (ref "U4") (pin "48") (pinfunction "P5.4/MCLK_48") (pintype "power_in+no_connect"))
    )
    (net (code "101") (name "unconnected-(U4-P5.5{slash}SMCLK-Pad49)") (class "Default")
      (node (ref "U4") (pin "49") (pinfunction "P5.5/SMCLK_49") (pintype "power_in+no_connect"))
    )
    (net (code "102") (name "unconnected-(U4-P5.6{slash}ACLK-Pad50)") (class "Default")
      (node (ref "U4") (pin "50") (pinfunction "P5.6/ACLK_50") (pintype "power_in+no_connect"))
    )
    (net (code "103") (name "unconnected-(U4-P5.7{slash}TBoutH-Pad51)") (class "Default")
      (node (ref "U4") (pin "51") (pinfunction "P5.7/TBoutH_51") (pintype "power_in+no_connect"))
    )
    (net (code "104") (name "unconnected-(U4-VREF+-Pad7)") (class "Default")
      (node (ref "U4") (pin "7") (pinfunction "VREF+_7") (pintype "power_in+no_connect"))
    )
    (net (code "105") (name "unconnected-(U4-VREF-{slash}VeREF--Pad11)") (class "Default")
      (node (ref "U4") (pin "11") (pinfunction "VREF-/VeREF-_11") (pintype "power_in+no_connect"))
    )
    (net (code "106") (name "unconnected-(U4-VeREF+-Pad10)") (class "Default")
      (node (ref "U4") (pin "10") (pinfunction "VeREF+_10") (pintype "power_in+no_connect"))
    )
    (net (code "107") (name "unconnected-(U4-XIN-Pad8)") (class "Default")
      (node (ref "U4") (pin "8") (pinfunction "XIN_8") (pintype "power_in+no_connect"))
    )
    (net (code "108") (name "unconnected-(U4-XOUT{slash}TCLK-Pad9)") (class "Default")
      (node (ref "U4") (pin "9") (pinfunction "XOUT/TCLK_9") (pintype "power_in+no_connect"))
    )
    (net (code "109") (name "unconnected-(U4-XT2IN-Pad53)") (class "Default")
      (node (ref "U4") (pin "53") (pinfunction "XT2IN_53") (pintype "power_in+no_connect"))
    )
    (net (code "110") (name "unconnected-(U4-XT2OUT-Pad52)") (class "Default")
      (node (ref "U4") (pin "52") (pinfunction "XT2OUT_52") (pintype "power_in+no_connect"))
    )
    (net (code "111") (name "unconnected-(U6-Pad10)") (class "Default")
      (node (ref "U6") (pin "10") (pinfunction "10_10") (pintype "passive+no_connect"))
    )
    (net (code "112") (name "unconnected-(U6-Pad13)") (class "Default")
      (node (ref "U6") (pin "13") (pinfunction "13_13") (pintype "passive+no_connect"))
    )
    (net (code "113") (name "unconnected-(U6-Pad14)") (class "Default")
      (node (ref "U6") (pin "14") (pinfunction "14_14") (pintype "passive+no_connect"))
    )
    (net (code "114") (name "unconnected-(U6-Pad15)") (class "Default")
      (node (ref "U6") (pin "15") (pinfunction "15_15") (pintype "passive+no_connect"))
    )
    (net (code "115") (name "unconnected-(U6-Pad16)") (class "Default")
      (node (ref "U6") (pin "16") (pinfunction "16_16") (pintype "passive+no_connect"))
    )
    (net (code "116") (name "unconnected-(U6-Pad17)") (class "Default")
      (node (ref "U6") (pin "17") (pinfunction "17_17") (pintype "passive+no_connect"))
    )
    (net (code "117") (name "unconnected-(U6-Pad18)") (class "Default")
      (node (ref "U6") (pin "18") (pinfunction "18_18") (pintype "passive+no_connect"))
    )
    (net (code "118") (name "unconnected-(U6-Pad19)") (class "Default")
      (node (ref "U6") (pin "19") (pinfunction "19_19") (pintype "passive+no_connect"))
    )
    (net (code "119") (name "unconnected-(U6-Pad20)") (class "Default")
      (node (ref "U6") (pin "20") (pinfunction "20_20") (pintype "passive+no_connect"))
    )
    (net (code "120") (name "unconnected-(U6-Pad21)") (class "Default")
      (node (ref "U6") (pin "21") (pinfunction "21_21") (pintype "passive+no_connect"))
    )
    (net (code "121") (name "unconnected-(U6-Pad22)") (class "Default")
      (node (ref "U6") (pin "22") (pinfunction "22_22") (pintype "passive+no_connect"))
    )
    (net (code "122") (name "unconnected-(U6-SUBPEND-Pad12)") (class "Default")
      (node (ref "U6") (pin "12") (pinfunction "SUBPEND_12") (pintype "passive+no_connect"))
    )
  )
)
